# NMT_I2C_INT.net
KiCad netlist of a schematic drawn in Altium Designer
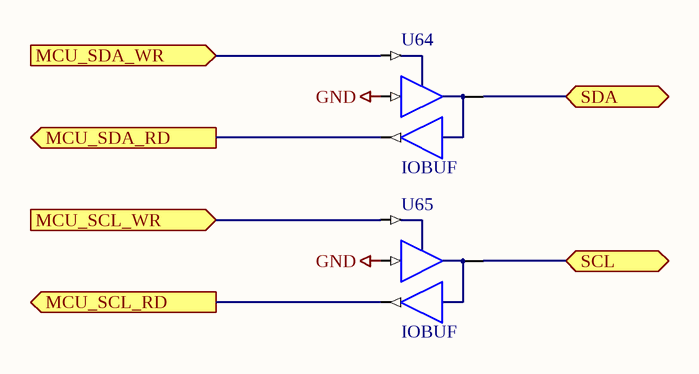
[diagram p0: NMT_I2C_INT.SCHDOC]

(export (version "E")
  (design (tool "Eeschema 10.0.6"))
  (components
    (comp (ref "U64")
      (value "IOBUF")
      (description "Input/Output Buffer")
      (fields (field (name "PUBLISHER") "Altium Limited"))
      (libsource (lib "FPGA Generic") (part "IOBUF"))
    )
    (comp (ref "U65")
      (value "IOBUF")
      (description "Input/Output Buffer")
      (fields (field (name "PUBLISHER") "Altium Limited"))
      (libsource (lib "FPGA Generic") (part "IOBUF"))
    )
  )
  (nets
    (net (code "1") (name "/MCU_SCL_RD") (class "Default")
      (node (ref "U65") (pin "O") (pinfunction "O_O") (pintype "output"))
    )
    (net (code "2") (name "/MCU_SCL_WR") (class "Default")
      (node (ref "U65") (pin "T") (pinfunction "T_T") (pintype "input"))
    )
    (net (code "3") (name "/MCU_SDA_RD") (class "Default")
      (node (ref "U64") (pin "O") (pinfunction "O_O") (pintype "output"))
    )
    (net (code "4") (name "/MCU_SDA_WR") (class "Default")
      (node (ref "U64") (pin "T") (pinfunction "T_T") (pintype "input"))
    )
    (net (code "5") (name "/SCL") (class "Default")
      (node (ref "U65") (pin "IO") (pinfunction "IO_IO") (pintype "bidirectional"))
    )
    (net (code "6") (name "/SDA") (class "Default")
      (node (ref "U64") (pin "IO") (pinfunction "IO_IO") (pintype "bidirectional"))
    )
    (net (code "7") (name "GND") (class "Default")
      (node (ref "U64") (pin "I") (pinfunction "I_I") (pintype "input"))
      (node (ref "U65") (pin "I") (pinfunction "I_I") (pintype "input"))
    )
  )
)
